# DSO_Power.net
KiCad netlist of a schematic drawn in Altium Designer
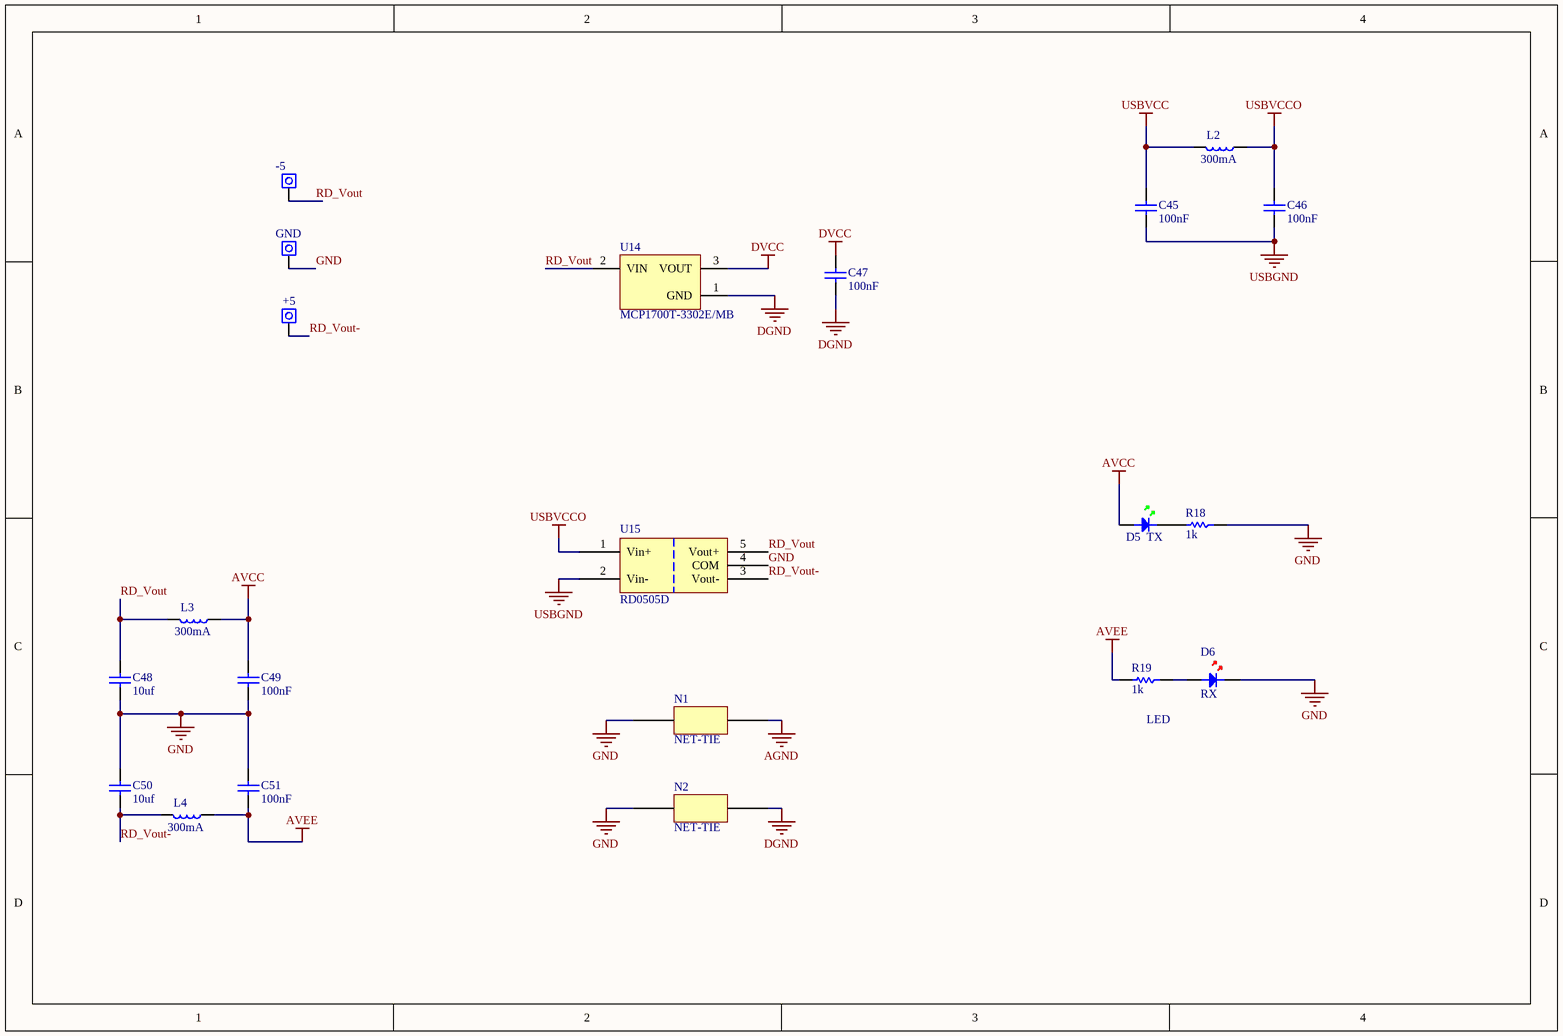
[diagram p0: DSO_Power.SchDoc]

(export (version "E")
  (design (tool "Eeschema 10.0.6"))
  (components
    (comp (ref "C45")
      (value "100nF")
      (footprint "0805C")
      (description "Capacitor")
      (fields (field (name "REVIEWED BY") "RM - 2018/08/05"))
      (libsource (lib "DSO") (part "C"))
    )
    (comp (ref "C46")
      (value "100nF")
      (footprint "0805C")
      (description "Capacitor")
      (fields (field (name "REVIEWED BY") "RM - 2018/08/05"))
      (libsource (lib "DSO") (part "C"))
    )
    (comp (ref "C47")
      (value "100nF")
      (footprint "0805C")
      (description "Capacitor")
      (fields (field (name "REVIEWED BY") "RM - 2018/08/05"))
      (libsource (lib "DSO") (part "C"))
    )
    (comp (ref "C48")
      (value "10uf")
      (footprint "0805C")
      (description "Capacitor")
      (fields (field (name "REVIEWED BY") "RM - 2018/08/05"))
      (libsource (lib "DSO") (part "C"))
    )
    (comp (ref "C49")
      (value "100nF")
      (footprint "0805C")
      (description "Capacitor")
      (fields (field (name "REVIEWED BY") "RM - 2018/08/05"))
      (libsource (lib "DSO") (part "C"))
    )
    (comp (ref "C50")
      (value "10uf")
      (footprint "0805C")
      (description "Capacitor")
      (fields (field (name "REVIEWED BY") "RM - 2018/08/05"))
      (libsource (lib "DSO") (part "C"))
    )
    (comp (ref "C51")
      (value "100nF")
      (footprint "0805C")
      (description "Capacitor")
      (fields (field (name "REVIEWED BY") "RM - 2018/08/05"))
      (libsource (lib "DSO") (part "C"))
    )
    (comp (ref "D5")
      (value "TX")
      (footprint "0805D-GREEN")
      (description "Light Emitting Diode")
      (fields (field (name "REVIEWED BY") "RM - 2018/08/05"))
      (libsource (lib "DSO") (part "LED GREEN"))
    )
    (comp (ref "D6")
      (value "RX")
      (footprint "0805D-RED")
      (description "Light Emitting Diode")
      (fields (field (name "REVIEWED BY") "RM - 2018/08/05"))
      (libsource (lib "DSO") (part "LED RED"))
    )
    (comp (ref "L2")
      (value "300mA")
      (footprint "0805")
      (description "Inductor")
      (fields (field (name "REVIEWED BY") "RM - 2018/08/05"))
      (libsource (lib "DSO") (part "I"))
    )
    (comp (ref "L3")
      (value "300mA")
      (footprint "0805")
      (description "Inductor")
      (fields (field (name "REVIEWED BY") "RM - 2018/08/05"))
      (libsource (lib "DSO") (part "I"))
    )
    (comp (ref "L4")
      (value "300mA")
      (footprint "0805")
      (description "Inductor")
      (fields (field (name "REVIEWED BY") "RM - 2018/08/05"))
      (libsource (lib "DSO") (part "I"))
    )
    (comp (ref "N1") (value "NET-TIE") (footprint "NET-TIE") (libsource (lib "RPOT") (part "NET-TIE")))
    (comp (ref "N2") (value "NET-TIE") (footprint "NET-TIE") (libsource (lib "RPOT") (part "NET-TIE")))
    (comp (ref "R18")
      (value "1k")
      (footprint "0805")
      (description "Resistor")
      (fields (field (name "REVIEWED BY") "RM - 2018/08/05"))
      (libsource (lib "DSO") (part "R"))
    )
    (comp (ref "R19")
      (value "1k")
      (footprint "0805")
      (description "Resistor")
      (fields (field (name "REVIEWED BY") "RM - 2018/08/05"))
      (libsource (lib "DSO") (part "R"))
    )
    (comp (ref "TP4")
      (value "-5")
      (footprint "PIN 1.8mm")
      (description "Pad")
      (libsource (lib "DSO") (part "WIRE"))
    )
    (comp (ref "TP5")
      (value "GND")
      (footprint "PIN 1.8mm")
      (description "Pad")
      (libsource (lib "DSO") (part "WIRE"))
    )
    (comp (ref "TP6")
      (value "+5")
      (footprint "PIN 1.8mm")
      (description "Pad")
      (libsource (lib "DSO") (part "WIRE"))
    )
    (comp (ref "U14")
      (value "MCP1700T-3302E/MB")
      (footprint "SOT89")
      (description "Low Quiescent Current LDO, 3-Pin SOT-89, Extended Temperature, Tape and Reel")
      (fields (field (name "REVIEWED BY") "RM - 2018/08/05"))
      (libsource (lib "DSO") (part "MCP1700T"))
    )
    (comp (ref "U15")
      (value "RD0505D")
      (footprint "SIP_NMG")
      (description "(ADV) DC to DC converter 5V in +-5V out")
      (fields (field (name "REVIEWED BY") "RM - 2018/08/05"))
      (libsource (lib "DSO") (part "RD0505D"))
    )
  )
  (nets
    (net (code "1") (name "/RD_Vout") (class "Default")
      (node (ref "C48") (pin "1") (pinfunction "1_1") (pintype "passive"))
      (node (ref "L3") (pin "2") (pinfunction "2_2") (pintype "passive"))
      (node (ref "TP4") (pin "1") (pintype "passive"))
      (node (ref "U14") (pin "2") (pinfunction "VIN_2") (pintype "power_in"))
      (node (ref "U15") (pin "5") (pinfunction "Vout+_5") (pintype "passive"))
    )
    (net (code "2") (name "/RD_Vout-") (class "Default")
      (node (ref "C50") (pin "2") (pinfunction "2_2") (pintype "passive"))
      (node (ref "L4") (pin "2") (pinfunction "2_2") (pintype "passive"))
      (node (ref "TP6") (pin "1") (pintype "passive"))
      (node (ref "U15") (pin "3") (pinfunction "Vout-_3") (pintype "passive"))
    )
    (net (code "3") (name "AGND") (class "Default")
      (node (ref "N1") (pin "1") (pinfunction "1_1") (pintype "passive"))
    )
    (net (code "4") (name "AVCC") (class "Default")
      (node (ref "C49") (pin "1") (pinfunction "1_1") (pintype "passive"))
      (node (ref "D5") (pin "A") (pinfunction "A_A") (pintype "passive"))
      (node (ref "L3") (pin "1") (pinfunction "1_1") (pintype "passive"))
    )
    (net (code "5") (name "AVEE") (class "Default")
      (node (ref "C51") (pin "2") (pinfunction "2_2") (pintype "passive"))
      (node (ref "L4") (pin "1") (pinfunction "1_1") (pintype "passive"))
      (node (ref "R19") (pin "2") (pintype "passive"))
    )
    (net (code "6") (name "DGND") (class "Default")
      (node (ref "C47") (pin "2") (pinfunction "2_2") (pintype "passive"))
      (node (ref "N2") (pin "1") (pinfunction "1_1") (pintype "passive"))
      (node (ref "U14") (pin "1") (pinfunction "GND_1") (pintype "power_in"))
    )
    (net (code "7") (name "DVCC") (class "Default")
      (node (ref "C47") (pin "1") (pinfunction "1_1") (pintype "passive"))
      (node (ref "U14") (pin "3") (pinfunction "VOUT_3") (pintype "power_in"))
    )
    (net (code "8") (name "GND") (class "Default")
      (node (ref "C48") (pin "2") (pinfunction "2_2") (pintype "passive"))
      (node (ref "C49") (pin "2") (pinfunction "2_2") (pintype "passive"))
      (node (ref "C50") (pin "1") (pinfunction "1_1") (pintype "passive"))
      (node (ref "C51") (pin "1") (pinfunction "1_1") (pintype "passive"))
      (node (ref "D6") (pin "A") (pinfunction "A_A") (pintype "passive"))
      (node (ref "N1") (pin "0") (pinfunction "0_0") (pintype "passive"))
      (node (ref "N2") (pin "0") (pinfunction "0_0") (pintype "passive"))
      (node (ref "R18") (pin "1") (pintype "passive"))
      (node (ref "TP5") (pin "1") (pintype "passive"))
      (node (ref "U15") (pin "4") (pinfunction "COM_4") (pintype "passive"))
    )
    (net (code "9") (name "Net-(D5-PadK)") (class "Default")
      (node (ref "D5") (pin "K") (pinfunction "K_K") (pintype "passive"))
      (node (ref "R18") (pin "2") (pintype "passive"))
    )
    (net (code "10") (name "Net-(D6-PadK)") (class "Default")
      (node (ref "D6") (pin "K") (pinfunction "K_K") (pintype "passive"))
      (node (ref "R19") (pin "1") (pintype "passive"))
    )
    (net (code "11") (name "USBGND") (class "Default")
      (node (ref "C45") (pin "2") (pinfunction "2_2") (pintype "passive"))
      (node (ref "C46") (pin "2") (pinfunction "2_2") (pintype "passive"))
      (node (ref "U15") (pin "2") (pinfunction "Vin-_2") (pintype "passive"))
    )
    (net (code "12") (name "USBVCC") (class "Default")
      (node (ref "C45") (pin "1") (pinfunction "1_1") (pintype "passive"))
      (node (ref "L2") (pin "2") (pinfunction "2_2") (pintype "passive"))
    )
    (net (code "13") (name "USBVCCO") (class "Default")
      (node (ref "C46") (pin "1") (pinfunction "1_1") (pintype "passive"))
      (node (ref "L2") (pin "1") (pinfunction "1_1") (pintype "passive"))
      (node (ref "U15") (pin "1") (pinfunction "Vin+_1") (pintype "passive"))
    )
  )
)
